# CON_PC-104_16bit_40PIN_PC104.net
KiCad netlist of a schematic drawn in Altium Designer
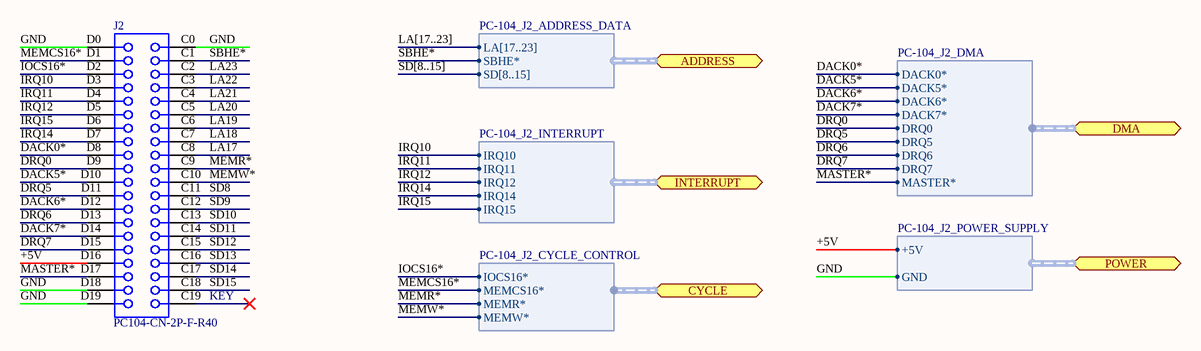
[diagram p0: CON_PC-104_16bit_40PIN_PC104.SchDoc]

(export (version "E")
  (design (tool "Eeschema 10.0.6"))
  (components
    (comp (ref "J2")
      (value "PC104-CN-2P-F-R40")
      (footprint "BTB2-54-V40F-04")
      (fields (field (name "PUBLISHER") "Altium"))
      (libsource (lib "Altium Shanghai") (part "PC104-CN-2P-F-R40"))
    )
  )
  (nets
    (net (code "6") (name "/+5V") (class "Default")
      (node (ref "J2") (pin "D16") (pinfunction "17_D16") (pintype "passive"))
    )
    (net (code "7") (name "/DACK0*") (class "Default")
      (node (ref "J2") (pin "D8") (pinfunction "9_D8") (pintype "passive"))
    )
    (net (code "8") (name "/DACK5*") (class "Default")
      (node (ref "J2") (pin "D10") (pinfunction "11_D10") (pintype "passive"))
    )
    (net (code "9") (name "/DACK6*") (class "Default")
      (node (ref "J2") (pin "D12") (pinfunction "13_D12") (pintype "passive"))
    )
    (net (code "10") (name "/DACK7*") (class "Default")
      (node (ref "J2") (pin "D14") (pinfunction "15_D14") (pintype "passive"))
    )
    (net (code "11") (name "/DRQ0") (class "Default")
      (node (ref "J2") (pin "D9") (pinfunction "10_D9") (pintype "passive"))
    )
    (net (code "12") (name "/DRQ5") (class "Default")
      (node (ref "J2") (pin "D11") (pinfunction "12_D11") (pintype "passive"))
    )
    (net (code "13") (name "/DRQ6") (class "Default")
      (node (ref "J2") (pin "D13") (pinfunction "14_D13") (pintype "passive"))
    )
    (net (code "14") (name "/DRQ7") (class "Default")
      (node (ref "J2") (pin "D15") (pinfunction "16_D15") (pintype "passive"))
    )
    (net (code "15") (name "/GND") (class "Default")
      (node (ref "J2") (pin "C0") (pinfunction "21_C0") (pintype "passive"))
      (node (ref "J2") (pin "D0") (pinfunction "1_D0") (pintype "passive"))
      (node (ref "J2") (pin "D18") (pinfunction "19_D18") (pintype "passive"))
      (node (ref "J2") (pin "D19") (pinfunction "20_D19") (pintype "passive"))
    )
    (net (code "16") (name "/IOCS16*") (class "Default")
      (node (ref "J2") (pin "D2") (pinfunction "3_D2") (pintype "passive"))
    )
    (net (code "17") (name "/IRQ10") (class "Default")
      (node (ref "J2") (pin "D3") (pinfunction "4_D3") (pintype "passive"))
    )
    (net (code "18") (name "/IRQ11") (class "Default")
      (node (ref "J2") (pin "D4") (pinfunction "5_D4") (pintype "passive"))
    )
    (net (code "19") (name "/IRQ12") (class "Default")
      (node (ref "J2") (pin "D5") (pinfunction "6_D5") (pintype "passive"))
    )
    (net (code "20") (name "/IRQ14") (class "Default")
      (node (ref "J2") (pin "D7") (pinfunction "8_D7") (pintype "passive"))
    )
    (net (code "21") (name "/IRQ15") (class "Default")
      (node (ref "J2") (pin "D6") (pinfunction "7_D6") (pintype "passive"))
    )
    (net (code "22") (name "/LA17") (class "Default")
      (node (ref "J2") (pin "C8") (pinfunction "29_C8") (pintype "passive"))
    )
    (net (code "23") (name "/LA18") (class "Default")
      (node (ref "J2") (pin "C7") (pinfunction "28_C7") (pintype "passive"))
    )
    (net (code "24") (name "/LA19") (class "Default")
      (node (ref "J2") (pin "C6") (pinfunction "27_C6") (pintype "passive"))
    )
    (net (code "25") (name "/LA20") (class "Default")
      (node (ref "J2") (pin "C5") (pinfunction "26_C5") (pintype "passive"))
    )
    (net (code "26") (name "/LA21") (class "Default")
      (node (ref "J2") (pin "C4") (pinfunction "25_C4") (pintype "passive"))
    )
    (net (code "27") (name "/LA22") (class "Default")
      (node (ref "J2") (pin "C3") (pinfunction "24_C3") (pintype "passive"))
    )
    (net (code "28") (name "/LA23") (class "Default")
      (node (ref "J2") (pin "C2") (pinfunction "23_C2") (pintype "passive"))
    )
    (net (code "30") (name "/MASTER*") (class "Default")
      (node (ref "J2") (pin "D17") (pinfunction "18_D17") (pintype "passive"))
    )
    (net (code "31") (name "/MEMCS16*") (class "Default")
      (node (ref "J2") (pin "D1") (pinfunction "2_D1") (pintype "passive"))
    )
    (net (code "32") (name "/MEMR*") (class "Default")
      (node (ref "J2") (pin "C9") (pinfunction "30_C9") (pintype "passive"))
    )
    (net (code "33") (name "/MEMW*") (class "Default")
      (node (ref "J2") (pin "C10") (pinfunction "31_C10") (pintype "passive"))
    )
    (net (code "34") (name "/SBHE*") (class "Default")
      (node (ref "J2") (pin "C1") (pinfunction "22_C1") (pintype "passive"))
    )
    (net (code "35") (name "/SD8") (class "Default")
      (node (ref "J2") (pin "C11") (pinfunction "32_C11") (pintype "passive"))
    )
    (net (code "36") (name "/SD9") (class "Default")
      (node (ref "J2") (pin "C12") (pinfunction "33_C12") (pintype "passive"))
    )
    (net (code "37") (name "/SD10") (class "Default")
      (node (ref "J2") (pin "C13") (pinfunction "34_C13") (pintype "passive"))
    )
    (net (code "38") (name "/SD11") (class "Default")
      (node (ref "J2") (pin "C14") (pinfunction "35_C14") (pintype "passive"))
    )
    (net (code "39") (name "/SD12") (class "Default")
      (node (ref "J2") (pin "C15") (pinfunction "36_C15") (pintype "passive"))
    )
    (net (code "40") (name "/SD13") (class "Default")
      (node (ref "J2") (pin "C16") (pinfunction "37_C16") (pintype "passive"))
    )
    (net (code "41") (name "/SD14") (class "Default")
      (node (ref "J2") (pin "C17") (pinfunction "38_C17") (pintype "passive"))
    )
    (net (code "42") (name "/SD15") (class "Default")
      (node (ref "J2") (pin "C18") (pinfunction "39_C18") (pintype "passive"))
    )
    (net (code "49") (name "unconnected-(J2-40-PadC19)") (class "Default")
      (node (ref "J2") (pin "C19") (pinfunction "40_C19") (pintype "passive+no_connect"))
    )
  )
)
